# QuadraticConverterSch.net
KiCad netlist of a schematic drawn in Altium Designer
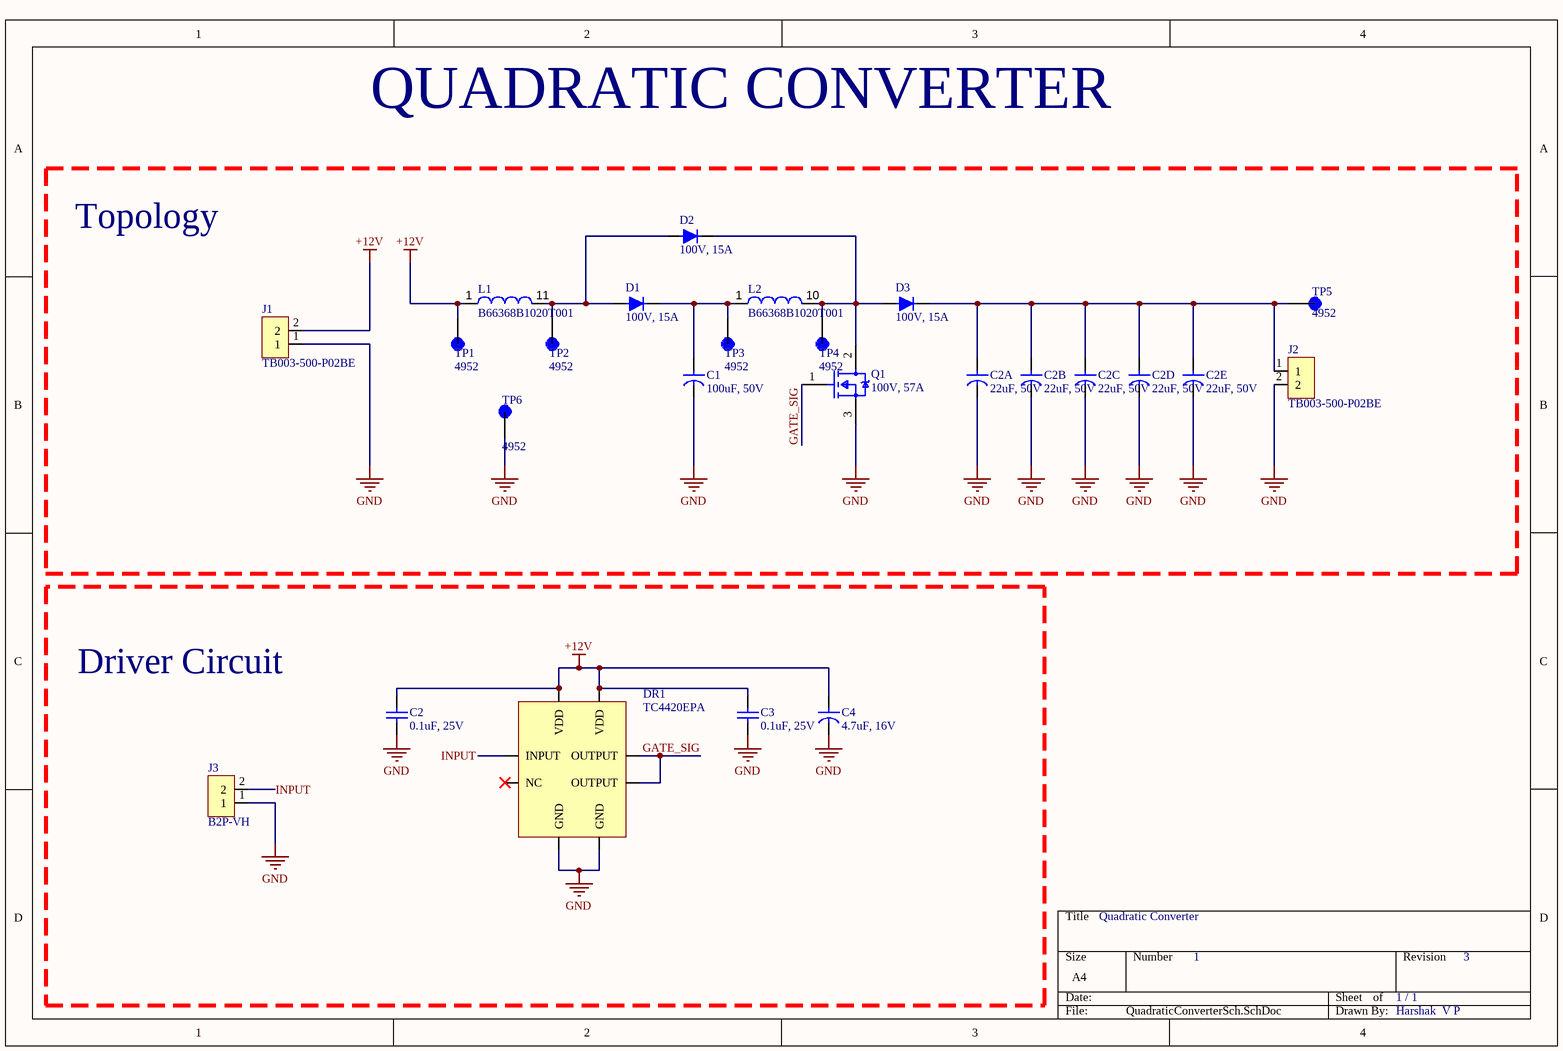
[diagram p0: QuadraticConverterSch.SchDoc]

(export (version "E")
  (design (tool "Eeschema 10.0.6"))
  (components
    (comp (ref "C1")
      (value "100uF, 50V")
      (footprint "CAP_G3")
      (description "CAP ALUM 100UF 20% 50V RADIAL TH")
      (fields
        (field (name "MANUFACTURER") "Yageo Group")
        (field (name "MANUFACTURER PART NUMBER") "SK107M050AG3AAKPLP")
      )
      (libsource (lib "QuadraticConverterSchLib") (part "SK107M050AG3AAKPLP"))
    )
    (comp (ref "C2")
      (value "0.1uF, 25V")
      (footprint "CAP_CER")
      (description "CAP CER 0.1UF 25V C0G/NP0 RADIAL")
      (fields
        (field (name "MANUFACTURER") "Yageo Group")
        (field (name "MANUFACTURER PART NUMBER") "C320C104J3G5TA")
      )
      (libsource (lib "QuadraticConverterSchLib") (part "C320C104J3G5TA"))
    )
    (comp (ref "C2A")
      (value "22uF, 50V")
      (footprint "CAP_C3")
      (description "CAP ALUM 22UF 20% 50V RADIAL TH")
      (fields
        (field (name "MANUFACTURER") "Yageo Group")
        (field (name "MANUFACTURER PART NUMBER") "ESK226M050AC3FA")
      )
      (libsource (lib "QuadraticConverterSchLib") (part "ESK226M050AC3FA"))
    )
    (comp (ref "C2B")
      (value "22uF, 50V")
      (footprint "CAP_C3")
      (description "CAP ALUM 22UF 20% 50V RADIAL TH")
      (fields
        (field (name "MANUFACTURER") "Yageo Group")
        (field (name "MANUFACTURER PART NUMBER") "ESK226M050AC3FA")
      )
      (libsource (lib "QuadraticConverterSchLib") (part "ESK226M050AC3FA"))
    )
    (comp (ref "C2C")
      (value "22uF, 50V")
      (footprint "CAP_C3")
      (description "CAP ALUM 22UF 20% 50V RADIAL TH")
      (fields
        (field (name "MANUFACTURER") "Yageo Group")
        (field (name "MANUFACTURER PART NUMBER") "ESK226M050AC3FA")
      )
      (libsource (lib "QuadraticConverterSchLib") (part "ESK226M050AC3FA"))
    )
    (comp (ref "C2D")
      (value "22uF, 50V")
      (footprint "CAP_C3")
      (description "CAP ALUM 22UF 20% 50V RADIAL TH")
      (fields
        (field (name "MANUFACTURER") "Yageo Group")
        (field (name "MANUFACTURER PART NUMBER") "ESK226M050AC3FA")
      )
      (libsource (lib "QuadraticConverterSchLib") (part "ESK226M050AC3FA"))
    )
    (comp (ref "C2E")
      (value "22uF, 50V")
      (footprint "CAP_C3")
      (description "CAP ALUM 22UF 20% 50V RADIAL TH")
      (fields
        (field (name "MANUFACTURER") "Yageo Group")
        (field (name "MANUFACTURER PART NUMBER") "ESK226M050AC3FA")
      )
      (libsource (lib "QuadraticConverterSchLib") (part "ESK226M050AC3FA"))
    )
    (comp (ref "C3")
      (value "0.1uF, 25V")
      (footprint "CAP_CER")
      (description "CAP CER 0.1UF 25V C0G/NP0 RADIAL")
      (fields
        (field (name "MANUFACTURER") "Yageo Group")
        (field (name "MANUFACTURER PART NUMBER") "C320C104J3G5TA")
      )
      (libsource (lib "QuadraticConverterSchLib") (part "C320C104J3G5TA"))
    )
    (comp (ref "C4")
      (value "4.7uF, 16V")
      (footprint "CAP_C3")
      (description "CAP ALUM 4.7UF 20% 16V RADIAL TH")
      (fields
        (field (name "MANUFACTURER") "Yageo Group")
        (field (name "MANUFACTURER PART NUMBER") "SK475M016AC3AAKPLP")
      )
      (libsource (lib "QuadraticConverterSchLib") (part "SK475M016AC3AAKPLP"))
    )
    (comp (ref "D1")
      (value "100V, 15A")
      (footprint "TO-220AC_ONS")
      (description "DIODE STANDARD 200V 15A TO2202")
      (fields (field (name "MANUFACTURER") "onsemi") (field (name "MANUFACTURER PART NUMBER") "MUR1520G"))
      (libsource (lib "QuadraticConverterSchLib") (part "MUR1520G"))
    )
    (comp (ref "D2")
      (value "100V, 15A")
      (footprint "TO-220AC_ONS")
      (description "DIODE STANDARD 200V 15A TO2202")
      (fields (field (name "MANUFACTURER") "onsemi") (field (name "MANUFACTURER PART NUMBER") "MUR1520G"))
      (libsource (lib "QuadraticConverterSchLib") (part "MUR1520G"))
    )
    (comp (ref "D3")
      (value "100V, 15A")
      (footprint "TO-220AC_ONS")
      (description "DIODE STANDARD 200V 15A TO2202")
      (fields (field (name "MANUFACTURER") "onsemi") (field (name "MANUFACTURER PART NUMBER") "MUR1520G"))
      (libsource (lib "QuadraticConverterSchLib") (part "MUR1520G"))
    )
    (comp (ref "DR1")
      (value "TC4420EPA")
      (footprint "TC4420EPA")
      (description "IC GATE DRVR LOW-SIDE 8DIP")
      (fields (field (name "MANUFACTURER") "Microchip"))
      (libsource (lib "QuadraticConverterSchLib") (part "TC4420EPA"))
    )
    (comp (ref "J1")
      (value "TB003-500-P02BE")
      (footprint "CUI_TB003-500-P02BE")
      (description "TERMINAL BLOCK, SCREW TYPE, 5.00")
      (fields (field (name "MANUFACTURER") "Same Sky"))
      (libsource (lib "QuadraticConverterSchLib") (part "TB003-500-P02BE"))
    )
    (comp (ref "J2")
      (value "TB003-500-P02BE")
      (footprint "CUI_TB003-500-P02BE")
      (description "TERMINAL BLOCK, SCREW TYPE, 5.00")
      (fields (field (name "MANUFACTURER") "Same Sky"))
      (libsource (lib "") (part "TB003-500-P02BE_1"))
    )
    (comp (ref "J3")
      (value "B2P-VH")
      (footprint "JST_B2P-VH(LF)(SN)")
      (description "CONN HEADER VERT 2POS 3.96MM")
      (fields (field (name "MANUFACTURER") "JST"))
      (libsource (lib "QuadraticConverterSchLib") (part "B2P-VH"))
    )
    (comp (ref "L1")
      (value "B66368B1020T001")
      (footprint "ETD49")
      (description "BOBBIN COIL FORMER ETD 49X25X16")
      (fields (field (name "MANUFACTURER") "EPCOS"))
      (libsource (lib "QuadraticConverterSchLib") (part "B66368B1020T001"))
    )
    (comp (ref "L2")
      (value "B66368B1020T001")
      (footprint "ETD44")
      (description "BOBBIN COIL FORMER ETD 44X22X15")
      (fields
        (field (name "MANUFACTURER") "EPCOS")
        (field (name "MANUFACTURER PART NUMBER") "B66366B1018T001")
      )
      (libsource (lib "QuadraticConverterSchLib") (part "B66366B1018T001"))
    )
    (comp (ref "Q1")
      (value "100V, 57A")
      (footprint "FP-PG-TO220-3-MFG")
      (description "MOSFET N-CH 100V 57A TO220AB")
      (fields (field (name "MANUFACTURER") "Infineon") (field (name "MANUFACTURER PART NUMBER") "IRF3710PBF"))
      (libsource (lib "QuadraticConverterSchLib") (part "IRF3710PBF"))
    )
    (comp (ref "TP1")
      (value "4952")
      (footprint "KEYSTONE_4952")
      (description "PC TEST POINT LOOP")
      (fields (field (name "MANUFACTURER") "Keystone"))
      (libsource (lib "QuadraticConverterSchLib") (part "4952"))
    )
    (comp (ref "TP2")
      (value "4952")
      (footprint "KEYSTONE_4952")
      (description "PC TEST POINT LOOP")
      (fields (field (name "MANUFACTURER") "Keystone"))
      (libsource (lib "QuadraticConverterSchLib") (part "4952"))
    )
    (comp (ref "TP3")
      (value "4952")
      (footprint "KEYSTONE_4952")
      (description "PC TEST POINT LOOP")
      (fields (field (name "MANUFACTURER") "Keystone"))
      (libsource (lib "QuadraticConverterSchLib") (part "4952"))
    )
    (comp (ref "TP4")
      (value "4952")
      (footprint "KEYSTONE_4952")
      (description "PC TEST POINT LOOP")
      (fields (field (name "MANUFACTURER") "Keystone"))
      (libsource (lib "QuadraticConverterSchLib") (part "4952"))
    )
    (comp (ref "TP5")
      (value "4952")
      (footprint "KEYSTONE_4952")
      (description "PC TEST POINT LOOP")
      (fields (field (name "MANUFACTURER") "Keystone"))
      (libsource (lib "QuadraticConverterSchLib") (part "4952"))
    )
    (comp (ref "TP6")
      (value "4952")
      (footprint "KEYSTONE_4952")
      (description "PC TEST POINT LOOP")
      (fields (field (name "MANUFACTURER") "Keystone"))
      (libsource (lib "QuadraticConverterSchLib") (part "4952"))
    )
  )
  (nets
    (net (code "1") (name "+12V") (class "Default")
      (node (ref "C2") (pin "2") (pinfunction "2_2") (pintype "passive"))
      (node (ref "C3") (pin "2") (pinfunction "2_2") (pintype "passive"))
      (node (ref "C4") (pin "2") (pinfunction "2_2") (pintype "passive"))
      (node (ref "DR1") (pin "1") (pinfunction "VDD_1") (pintype "passive"))
      (node (ref "DR1") (pin "8") (pinfunction "VDD_8") (pintype "passive"))
      (node (ref "J1") (pin "2") (pinfunction "2_2") (pintype "passive"))
      (node (ref "L1") (pin "1") (pinfunction "1_1") (pintype "passive"))
      (node (ref "TP1") (pin "TP") (pinfunction "TP_TP") (pintype "passive"))
    )
    (net (code "2") (name "/GATE_SIG") (class "Default")
      (node (ref "DR1") (pin "6") (pinfunction "OUTPUT_6") (pintype "passive"))
      (node (ref "DR1") (pin "7") (pinfunction "OUTPUT_7") (pintype "passive"))
      (node (ref "Q1") (pin "1") (pinfunction "G_1") (pintype "passive"))
    )
    (net (code "3") (name "/INPUT") (class "Default")
      (node (ref "DR1") (pin "2") (pinfunction "INPUT_2") (pintype "passive"))
      (node (ref "J3") (pin "2") (pinfunction "2_2") (pintype "passive"))
    )
    (net (code "4") (name "GND") (class "Default")
      (node (ref "C1") (pin "1") (pinfunction "1_1") (pintype "passive"))
      (node (ref "C2") (pin "1") (pinfunction "1_1") (pintype "passive"))
      (node (ref "C2A") (pin "1") (pinfunction "1_1") (pintype "passive"))
      (node (ref "C2B") (pin "1") (pinfunction "1_1") (pintype "passive"))
      (node (ref "C2C") (pin "1") (pinfunction "1_1") (pintype "passive"))
      (node (ref "C2D") (pin "1") (pinfunction "1_1") (pintype "passive"))
      (node (ref "C2E") (pin "1") (pinfunction "1_1") (pintype "passive"))
      (node (ref "C3") (pin "1") (pinfunction "1_1") (pintype "passive"))
      (node (ref "C4") (pin "1") (pinfunction "1_1") (pintype "passive"))
      (node (ref "DR1") (pin "4") (pinfunction "GND_4") (pintype "passive"))
      (node (ref "DR1") (pin "5") (pinfunction "GND_5") (pintype "passive"))
      (node (ref "J1") (pin "1") (pinfunction "1_1") (pintype "passive"))
      (node (ref "J2") (pin "2") (pinfunction "2_2") (pintype "passive"))
      (node (ref "J3") (pin "1") (pinfunction "1_1") (pintype "passive"))
      (node (ref "Q1") (pin "3") (pinfunction "S_3") (pintype "passive"))
      (node (ref "TP6") (pin "TP") (pinfunction "TP_TP") (pintype "passive"))
    )
    (net (code "5") (name "Net-(C1-Pad2)") (class "Default")
      (node (ref "C1") (pin "2") (pinfunction "2_2") (pintype "passive"))
      (node (ref "D1") (pin "2") (pinfunction "2_2") (pintype "passive"))
      (node (ref "L2") (pin "1") (pinfunction "1_1") (pintype "passive"))
      (node (ref "TP3") (pin "TP") (pinfunction "TP_TP") (pintype "passive"))
    )
    (net (code "6") (name "Net-(C2A-Pad2)") (class "Default")
      (node (ref "C2A") (pin "2") (pinfunction "2_2") (pintype "passive"))
      (node (ref "C2B") (pin "2") (pinfunction "2_2") (pintype "passive"))
      (node (ref "C2C") (pin "2") (pinfunction "2_2") (pintype "passive"))
      (node (ref "C2D") (pin "2") (pinfunction "2_2") (pintype "passive"))
      (node (ref "C2E") (pin "2") (pinfunction "2_2") (pintype "passive"))
      (node (ref "D3") (pin "2") (pinfunction "2_2") (pintype "passive"))
      (node (ref "J2") (pin "1") (pinfunction "1_1") (pintype "passive"))
      (node (ref "TP5") (pin "TP") (pinfunction "TP_TP") (pintype "passive"))
    )
    (net (code "7") (name "Net-(D1-Pad1)") (class "Default")
      (node (ref "D1") (pin "1") (pinfunction "1_1") (pintype "passive"))
      (node (ref "D2") (pin "1") (pinfunction "1_1") (pintype "passive"))
      (node (ref "L1") (pin "11") (pinfunction "11_11") (pintype "passive"))
      (node (ref "TP2") (pin "TP") (pinfunction "TP_TP") (pintype "passive"))
    )
    (net (code "8") (name "Net-(Q1-D)") (class "Default")
      (node (ref "D2") (pin "2") (pinfunction "2_2") (pintype "passive"))
      (node (ref "D3") (pin "1") (pinfunction "1_1") (pintype "passive"))
      (node (ref "L2") (pin "10") (pinfunction "10_10") (pintype "passive"))
      (node (ref "Q1") (pin "2") (pinfunction "D_2") (pintype "passive"))
      (node (ref "TP4") (pin "TP") (pinfunction "TP_TP") (pintype "passive"))
    )
    (net (code "9") (name "unconnected-(DR1-NC-Pad3)") (class "Default")
      (node (ref "DR1") (pin "3") (pinfunction "NC_3") (pintype "passive+no_connect"))
    )
  )
)
